# 00_MAIN.net
KiCad netlist of a schematic drawn in Altium Designer
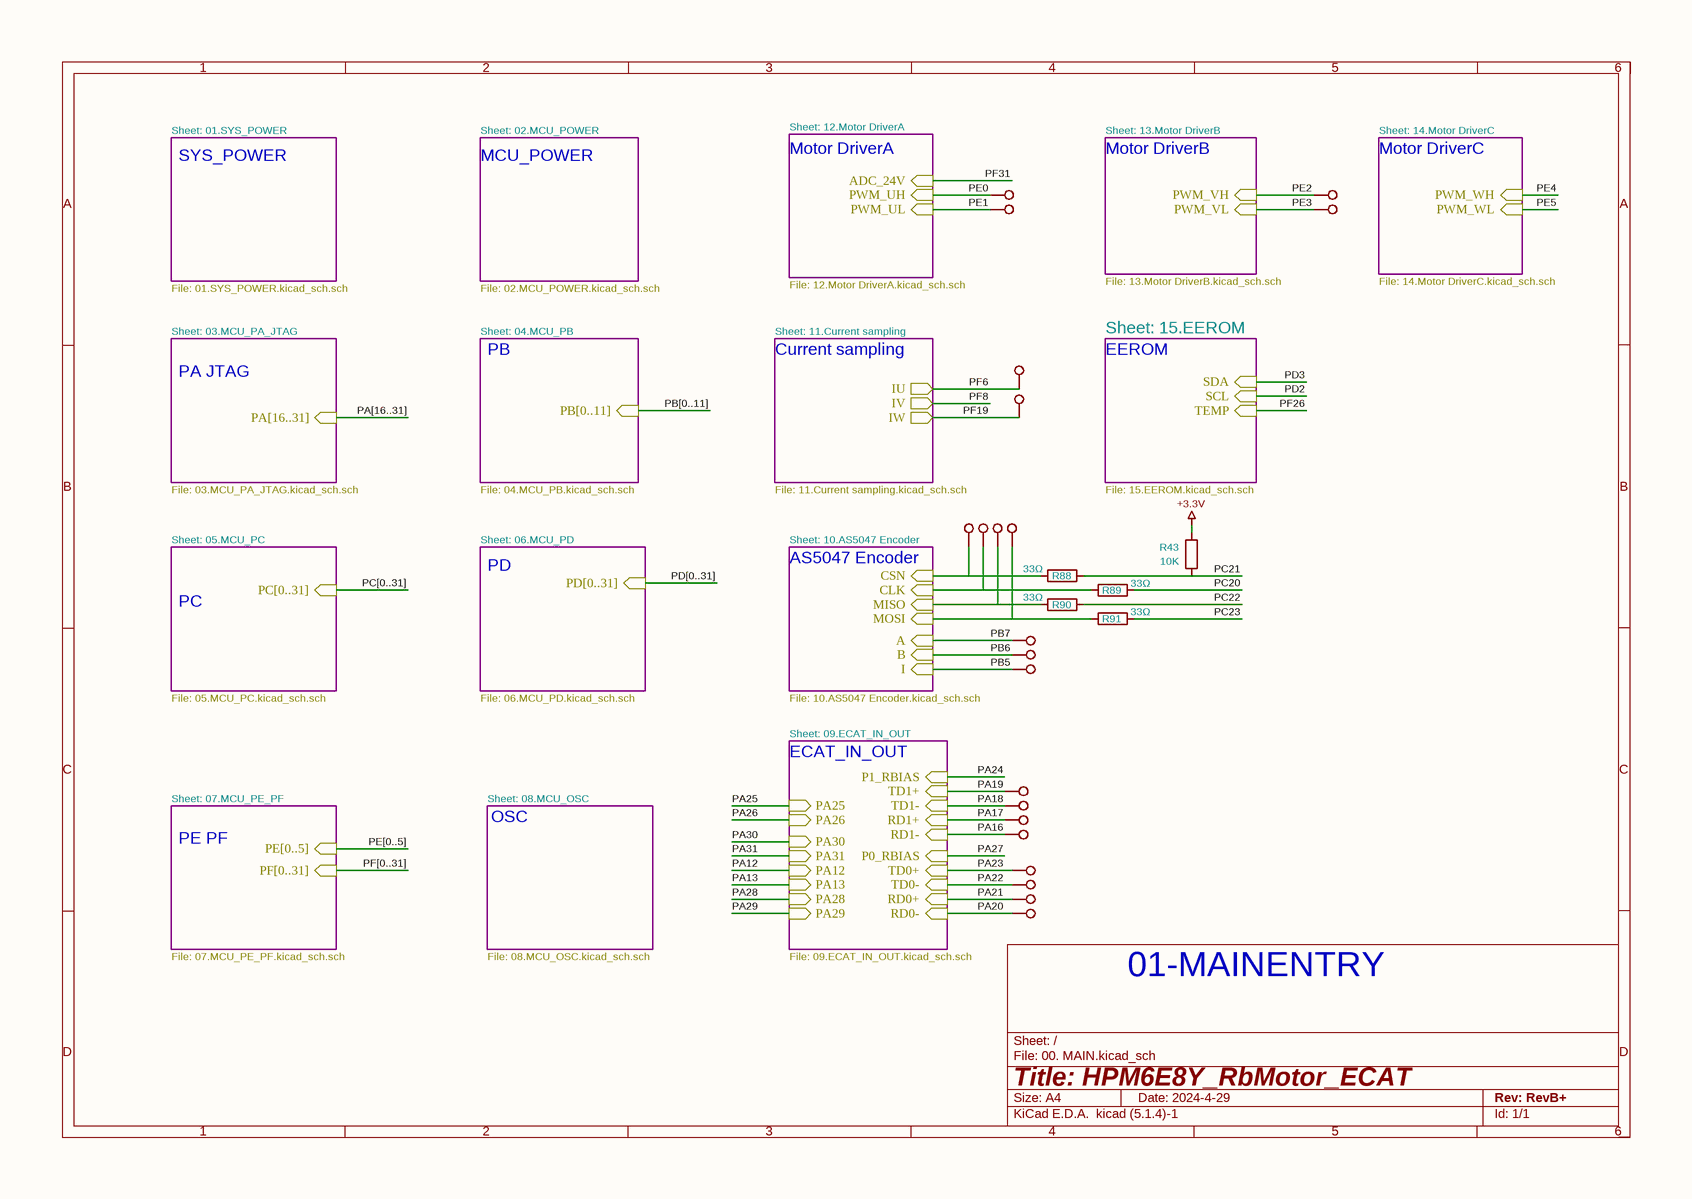
[diagram p0: 00. MAIN.SchDoc]

(export (version "E")
  (design (tool "Eeschema 10.0.6"))
  (components
    (comp (ref "R43") (value "10K") (libsource (lib "02_HPM_Resistor") (part "10K_0402")))
    (comp (ref "R88") (value "33Ω") (libsource (lib "02_HPM_Resistor") (part "33Ω_0402")))
    (comp (ref "R89") (value "33Ω") (libsource (lib "02_HPM_Resistor") (part "33Ω_0402")))
    (comp (ref "R90") (value "33Ω") (libsource (lib "02_HPM_Resistor") (part "33Ω_0402")))
    (comp (ref "R91") (value "33Ω") (libsource (lib "02_HPM_Resistor") (part "33Ω_0402")))
    (comp (ref "TP2") (value "0.5mm") (libsource (lib "01-HPM-Peripheral") (part "TestPoint-0.5mm")))
    (comp (ref "TP3") (value "0.5mm") (libsource (lib "01-HPM-Peripheral") (part "TestPoint-0.5mm")))
    (comp (ref "TP9") (value "0.5mm") (libsource (lib "01-HPM-Peripheral") (part "TestPoint-0.5mm")))
    (comp (ref "TP12") (value "0.5mm") (libsource (lib "01-HPM-Peripheral") (part "TestPoint-0.5mm")))
    (comp (ref "TP13") (value "0.5mm") (libsource (lib "01-HPM-Peripheral") (part "TestPoint-0.5mm")))
    (comp (ref "TP15") (value "0.5mm") (libsource (lib "01-HPM-Peripheral") (part "TestPoint-0.5mm")))
    (comp (ref "TP18") (value "0.5mm") (libsource (lib "01-HPM-Peripheral") (part "TestPoint-0.5mm")))
    (comp (ref "TP19") (value "0.5mm") (libsource (lib "01-HPM-Peripheral") (part "TestPoint-0.5mm")))
    (comp (ref "TP20") (value "0.5mm") (libsource (lib "01-HPM-Peripheral") (part "TestPoint-0.5mm")))
    (comp (ref "TP21") (value "0.5mm") (libsource (lib "01-HPM-Peripheral") (part "TestPoint-0.5mm")))
    (comp (ref "TP22") (value "0.5mm") (libsource (lib "01-HPM-Peripheral") (part "TestPoint-0.5mm")))
    (comp (ref "TP23") (value "0.5mm") (libsource (lib "01-HPM-Peripheral") (part "TestPoint-0.5mm")))
    (comp (ref "TP24") (value "0.5mm") (libsource (lib "01-HPM-Peripheral") (part "TestPoint-0.5mm")))
    (comp (ref "TP25") (value "0.5mm") (libsource (lib "01-HPM-Peripheral") (part "TestPoint-0.5mm")))
    (comp (ref "TP26") (value "0.5mm") (libsource (lib "01-HPM-Peripheral") (part "TestPoint-0.5mm")))
    (comp (ref "TP27") (value "0.5mm") (libsource (lib "01-HPM-Peripheral") (part "TestPoint-0.5mm")))
    (comp (ref "TP28") (value "0.5mm") (libsource (lib "01-HPM-Peripheral") (part "TestPoint-0.5mm")))
    (comp (ref "TP29") (value "0.5mm") (libsource (lib "01-HPM-Peripheral") (part "TestPoint-0.5mm")))
    (comp (ref "TP30") (value "0.5mm") (libsource (lib "01-HPM-Peripheral") (part "TestPoint-0.5mm")))
    (comp (ref "TP31") (value "0.5mm") (libsource (lib "01-HPM-Peripheral") (part "TestPoint-0.5mm")))
    (comp (ref "TP32") (value "0.5mm") (libsource (lib "01-HPM-Peripheral") (part "TestPoint-0.5mm")))
  )
  (nets
    (net (code "95") (name "+3.3V") (class "Default")
      (node (ref "R43") (pin "2") (pinfunction "2_2") (pintype "passive"))
    )
    (net (code "96") (name "/CLK") (class "Default")
      (node (ref "R89") (pin "1") (pinfunction "1_1") (pintype "passive"))
      (node (ref "TP19") (pin "1") (pinfunction "1_1") (pintype "passive"))
    )
    (net (code "97") (name "/CSN") (class "Default")
      (node (ref "R88") (pin "1") (pinfunction "1_1") (pintype "passive"))
      (node (ref "TP18") (pin "1") (pinfunction "1_1") (pintype "passive"))
    )
    (net (code "98") (name "/MISO") (class "Default")
      (node (ref "R90") (pin "1") (pinfunction "1_1") (pintype "passive"))
      (node (ref "TP20") (pin "1") (pinfunction "1_1") (pintype "passive"))
    )
    (net (code "99") (name "/MOSI") (class "Default")
      (node (ref "R91") (pin "1") (pinfunction "1_1") (pintype "passive"))
      (node (ref "TP21") (pin "1") (pinfunction "1_1") (pintype "passive"))
    )
    (net (code "102") (name "/PA16") (class "Default")
      (node (ref "TP25") (pin "1") (pinfunction "1_1") (pintype "passive"))
    )
    (net (code "103") (name "/PA17") (class "Default")
      (node (ref "TP24") (pin "1") (pinfunction "1_1") (pintype "passive"))
    )
    (net (code "104") (name "/PA18") (class "Default")
      (node (ref "TP23") (pin "1") (pinfunction "1_1") (pintype "passive"))
    )
    (net (code "105") (name "/PA19") (class "Default")
      (node (ref "TP22") (pin "1") (pinfunction "1_1") (pintype "passive"))
    )
    (net (code "106") (name "/PA20") (class "Default")
      (node (ref "TP29") (pin "1") (pinfunction "1_1") (pintype "passive"))
    )
    (net (code "107") (name "/PA21") (class "Default")
      (node (ref "TP28") (pin "1") (pinfunction "1_1") (pintype "passive"))
    )
    (net (code "108") (name "/PA22") (class "Default")
      (node (ref "TP27") (pin "1") (pinfunction "1_1") (pintype "passive"))
    )
    (net (code "109") (name "/PA23") (class "Default")
      (node (ref "TP26") (pin "1") (pinfunction "1_1") (pintype "passive"))
    )
    (net (code "119") (name "/PB5") (class "Default")
      (node (ref "TP32") (pin "1") (pinfunction "1_1") (pintype "passive"))
    )
    (net (code "120") (name "/PB6") (class "Default")
      (node (ref "TP31") (pin "1") (pinfunction "1_1") (pintype "passive"))
    )
    (net (code "121") (name "/PB7") (class "Default")
      (node (ref "TP30") (pin "1") (pinfunction "1_1") (pintype "passive"))
    )
    (net (code "123") (name "/PC20") (class "Default")
      (node (ref "R89") (pin "2") (pinfunction "2_2") (pintype "passive"))
    )
    (net (code "124") (name "/PC21") (class "Default")
      (node (ref "R43") (pin "1") (pinfunction "1_1") (pintype "passive"))
      (node (ref "R88") (pin "2") (pinfunction "2_2") (pintype "passive"))
    )
    (net (code "125") (name "/PC22") (class "Default")
      (node (ref "R90") (pin "2") (pinfunction "2_2") (pintype "passive"))
    )
    (net (code "126") (name "/PC23") (class "Default")
      (node (ref "R91") (pin "2") (pinfunction "2_2") (pintype "passive"))
    )
    (net (code "131") (name "/PE0") (class "Default")
      (node (ref "TP12") (pin "1") (pinfunction "1_1") (pintype "passive"))
    )
    (net (code "132") (name "/PE1") (class "Default")
      (node (ref "TP13") (pin "1") (pinfunction "1_1") (pintype "passive"))
    )
    (net (code "133") (name "/PE2") (class "Default")
      (node (ref "TP2") (pin "1") (pinfunction "1_1") (pintype "passive"))
    )
    (net (code "134") (name "/PE3") (class "Default")
      (node (ref "TP9") (pin "1") (pinfunction "1_1") (pintype "passive"))
    )
    (net (code "138") (name "/PF6") (class "Default")
      (node (ref "TP3") (pin "1") (pinfunction "1_1") (pintype "passive"))
    )
    (net (code "140") (name "/PF19") (class "Default")
      (node (ref "TP15") (pin "1") (pinfunction "1_1") (pintype "passive"))
    )
  )
)
